# v3-half.net
KiCad netlist of a schematic drawn in EAGLE
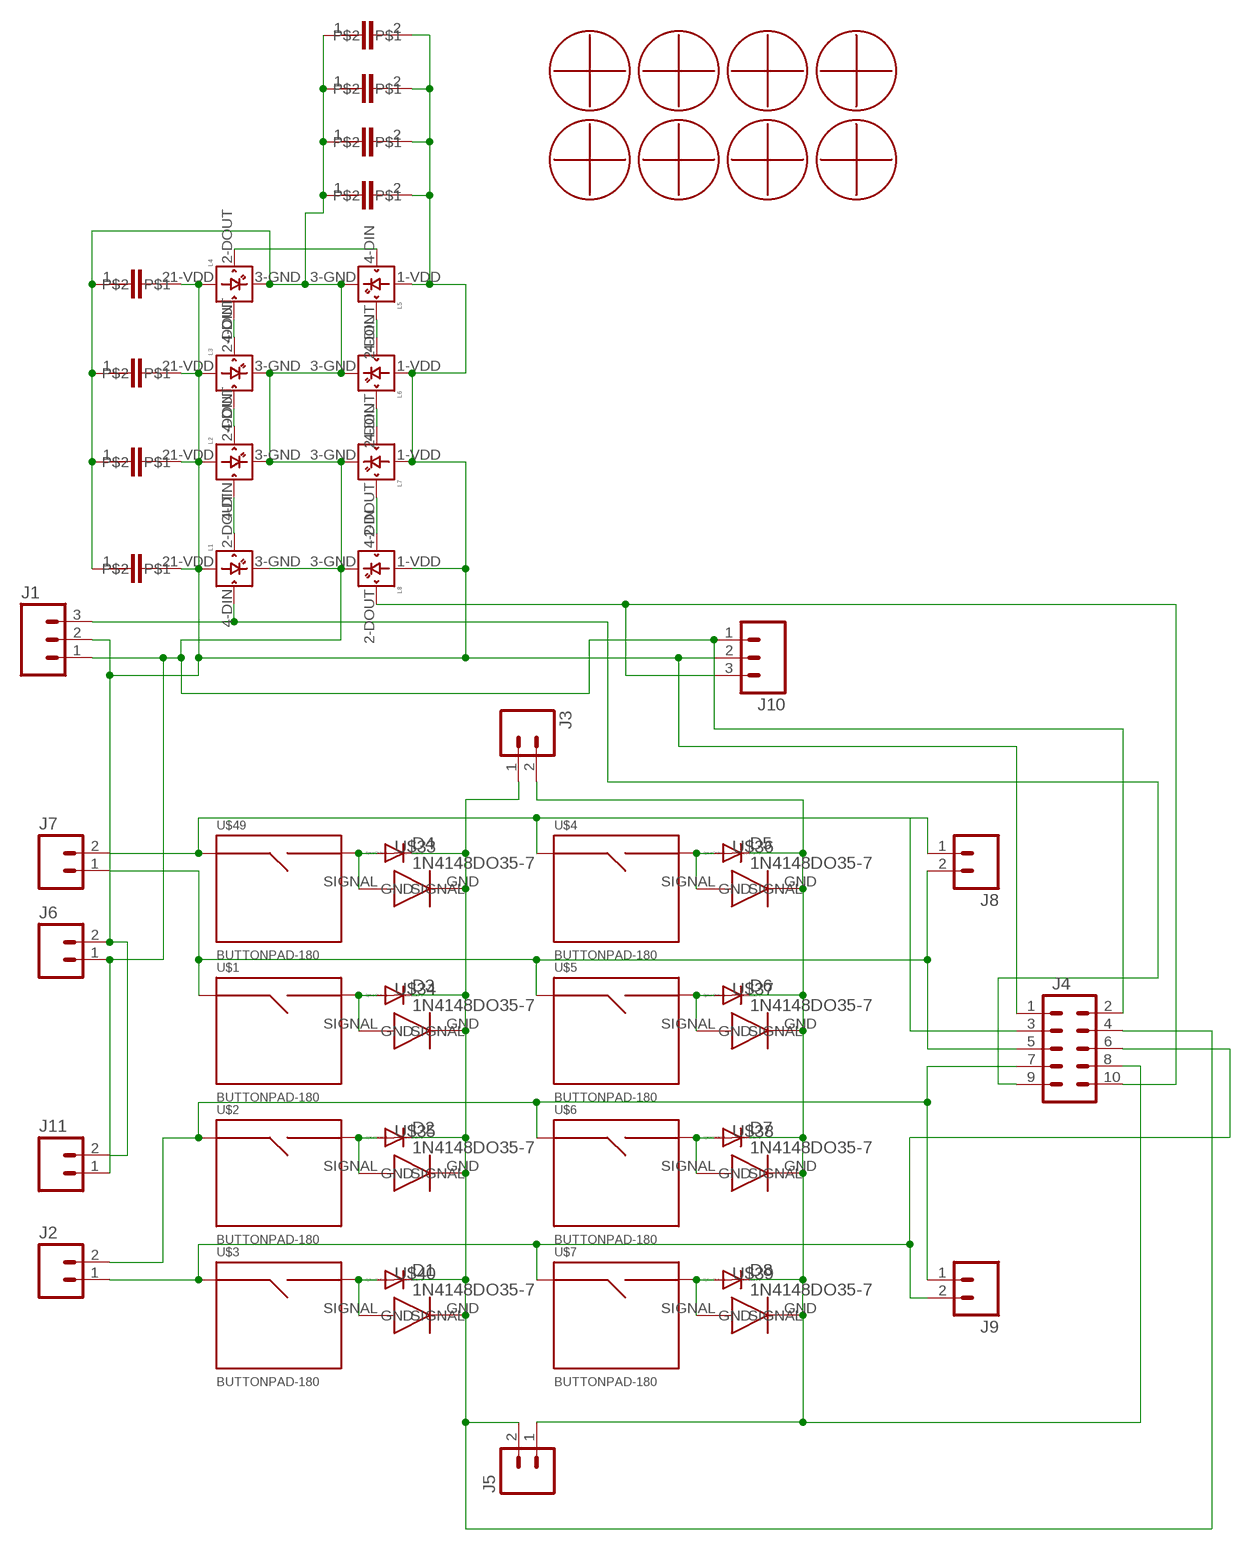
[diagram p0: schematic, sheet 1]

(export (version "E")
  (design (tool "Eeschema 10.0.6"))
  (components
    (comp (ref "D1")
      (value "1N4148DO35-7")
      (footprint "eagle-import:DO35-7")
      (libsource (lib "eagle-import") (part "1N4148DO35-7"))
    )
    (comp (ref "D2")
      (value "1N4148DO35-7")
      (footprint "eagle-import:DO35-7")
      (libsource (lib "eagle-import") (part "1N4148DO35-7"))
    )
    (comp (ref "D3")
      (value "1N4148DO35-7")
      (footprint "eagle-import:DO35-7")
      (libsource (lib "eagle-import") (part "1N4148DO35-7"))
    )
    (comp (ref "D4")
      (value "1N4148DO35-7")
      (footprint "eagle-import:DO35-7")
      (libsource (lib "eagle-import") (part "1N4148DO35-7"))
    )
    (comp (ref "D5")
      (value "1N4148DO35-7")
      (footprint "eagle-import:DO35-7")
      (libsource (lib "eagle-import") (part "1N4148DO35-7"))
    )
    (comp (ref "D6")
      (value "1N4148DO35-7")
      (footprint "eagle-import:DO35-7")
      (libsource (lib "eagle-import") (part "1N4148DO35-7"))
    )
    (comp (ref "D7")
      (value "1N4148DO35-7")
      (footprint "eagle-import:DO35-7")
      (libsource (lib "eagle-import") (part "1N4148DO35-7"))
    )
    (comp (ref "D8")
      (value "1N4148DO35-7")
      (footprint "eagle-import:DO35-7")
      (libsource (lib "eagle-import") (part "1N4148DO35-7"))
    )
    (comp (ref "J1")
      (value "M031X03_NO_SILK")
      (footprint "eagle-import:1X03_NO_SILK")
      (libsource (lib "eagle-import") (part "M031X03_NO_SILK"))
    )
    (comp (ref "J2")
      (value "M021X02_NO_SILK")
      (footprint "eagle-import:1X02_NO_SILK")
      (libsource (lib "eagle-import") (part "M021X02_NO_SILK"))
    )
    (comp (ref "J3")
      (value "M021X02_NO_SILK")
      (footprint "eagle-import:1X02_NO_SILK")
      (libsource (lib "eagle-import") (part "M021X02_NO_SILK"))
    )
    (comp (ref "J4")
      (value "M05X2NO_SILK")
      (footprint "eagle-import:2X5_NOSILK")
      (libsource (lib "eagle-import") (part "M05X2NO_SILK"))
    )
    (comp (ref "J5")
      (value "M021X02_NO_SILK")
      (footprint "eagle-import:1X02_NO_SILK")
      (libsource (lib "eagle-import") (part "M021X02_NO_SILK"))
    )
    (comp (ref "J6")
      (value "M021X02_NO_SILK")
      (footprint "eagle-import:1X02_NO_SILK")
      (libsource (lib "eagle-import") (part "M021X02_NO_SILK"))
    )
    (comp (ref "J7")
      (value "M021X02_NO_SILK")
      (footprint "eagle-import:1X02_NO_SILK")
      (libsource (lib "eagle-import") (part "M021X02_NO_SILK"))
    )
    (comp (ref "J8")
      (value "M021X02_NO_SILK")
      (footprint "eagle-import:1X02_NO_SILK")
      (libsource (lib "eagle-import") (part "M021X02_NO_SILK"))
    )
    (comp (ref "J9")
      (value "M021X02_NO_SILK")
      (footprint "eagle-import:1X02_NO_SILK")
      (libsource (lib "eagle-import") (part "M021X02_NO_SILK"))
    )
    (comp (ref "J10")
      (value "M031X03_NO_SILK")
      (footprint "eagle-import:1X03_NO_SILK")
      (libsource (lib "eagle-import") (part "M031X03_NO_SILK"))
    )
    (comp (ref "J11")
      (value "M021X02_NO_SILK")
      (footprint "eagle-import:1X02_NO_SILK")
      (libsource (lib "eagle-import") (part "M021X02_NO_SILK"))
    )
    (comp (ref "L1")
      (value "WS2812B")
      (footprint "eagle-import:WS2812B")
      (libsource (lib "eagle-import") (part "WS2812B"))
    )
    (comp (ref "L2")
      (value "WS2812B")
      (footprint "eagle-import:WS2812B")
      (libsource (lib "eagle-import") (part "WS2812B"))
    )
    (comp (ref "L3")
      (value "WS2812B")
      (footprint "eagle-import:WS2812B")
      (libsource (lib "eagle-import") (part "WS2812B"))
    )
    (comp (ref "L4")
      (value "WS2812B")
      (footprint "eagle-import:WS2812B")
      (libsource (lib "eagle-import") (part "WS2812B"))
    )
    (comp (ref "L5")
      (value "WS2812B")
      (footprint "eagle-import:WS2812B")
      (libsource (lib "eagle-import") (part "WS2812B"))
    )
    (comp (ref "L6")
      (value "WS2812B")
      (footprint "eagle-import:WS2812B")
      (libsource (lib "eagle-import") (part "WS2812B"))
    )
    (comp (ref "L7")
      (value "WS2812B")
      (footprint "eagle-import:WS2812B")
      (libsource (lib "eagle-import") (part "WS2812B"))
    )
    (comp (ref "L8")
      (value "WS2812B")
      (footprint "eagle-import:WS2812B")
      (libsource (lib "eagle-import") (part "WS2812B"))
    )
    (comp (ref "U$1")
      (value "BUTTONPAD-180")
      (footprint "eagle-import:BUTTONPAD-180")
      (libsource (lib "eagle-import") (part "BUTTONPAD-180"))
    )
    (comp (ref "U$2")
      (value "BUTTONPAD-180")
      (footprint "eagle-import:BUTTONPAD-180")
      (libsource (lib "eagle-import") (part "BUTTONPAD-180"))
    )
    (comp (ref "U$3")
      (value "BUTTONPAD-180")
      (footprint "eagle-import:BUTTONPAD-180")
      (libsource (lib "eagle-import") (part "BUTTONPAD-180"))
    )
    (comp (ref "U$4")
      (value "BUTTONPAD-180")
      (footprint "eagle-import:BUTTONPAD-180")
      (libsource (lib "eagle-import") (part "BUTTONPAD-180"))
    )
    (comp (ref "U$5")
      (value "BUTTONPAD-180")
      (footprint "eagle-import:BUTTONPAD-180")
      (libsource (lib "eagle-import") (part "BUTTONPAD-180"))
    )
    (comp (ref "U$6")
      (value "BUTTONPAD-180")
      (footprint "eagle-import:BUTTONPAD-180")
      (libsource (lib "eagle-import") (part "BUTTONPAD-180"))
    )
    (comp (ref "U$7")
      (value "BUTTONPAD-180")
      (footprint "eagle-import:BUTTONPAD-180")
      (libsource (lib "eagle-import") (part "BUTTONPAD-180"))
    )
    (comp (ref "U$8")
      (value "M25MOUNT")
      (footprint "eagle-import:M25MOUNT")
      (libsource (lib "eagle-import") (part "M25MOUNT"))
    )
    (comp (ref "U$9")
      (value "M25MOUNT")
      (footprint "eagle-import:M25MOUNT")
      (libsource (lib "eagle-import") (part "M25MOUNT"))
    )
    (comp (ref "U$10")
      (value "M25MOUNT")
      (footprint "eagle-import:M25MOUNT")
      (libsource (lib "eagle-import") (part "M25MOUNT"))
    )
    (comp (ref "U$11")
      (value "M25MOUNT")
      (footprint "eagle-import:M25MOUNT")
      (libsource (lib "eagle-import") (part "M25MOUNT"))
    )
    (comp (ref "U$12")
      (value "M25MOUNT")
      (footprint "eagle-import:M25MOUNT")
      (libsource (lib "eagle-import") (part "M25MOUNT"))
    )
    (comp (ref "U$13")
      (value "M25MOUNT")
      (footprint "eagle-import:M25MOUNT")
      (libsource (lib "eagle-import") (part "M25MOUNT"))
    )
    (comp (ref "U$14")
      (value "M25MOUNT")
      (footprint "eagle-import:M25MOUNT")
      (libsource (lib "eagle-import") (part "M25MOUNT"))
    )
    (comp (ref "U$15")
      (value "M25MOUNT")
      (footprint "eagle-import:M25MOUNT")
      (libsource (lib "eagle-import") (part "M25MOUNT"))
    )
    (comp (ref "U$17")
      (value "0805CAP")
      (footprint "eagle-import:0805")
      (libsource (lib "eagle-import") (part "0805CAP"))
    )
    (comp (ref "U$18")
      (value "0805CAP")
      (footprint "eagle-import:0805")
      (libsource (lib "eagle-import") (part "0805CAP"))
    )
    (comp (ref "U$19")
      (value "0805CAP")
      (footprint "eagle-import:0805")
      (libsource (lib "eagle-import") (part "0805CAP"))
    )
    (comp (ref "U$20")
      (value "0805CAP")
      (footprint "eagle-import:0805")
      (libsource (lib "eagle-import") (part "0805CAP"))
    )
    (comp (ref "U$25")
      (value "0805CAP")
      (footprint "eagle-import:0805")
      (libsource (lib "eagle-import") (part "0805CAP"))
    )
    (comp (ref "U$26")
      (value "0805CAP")
      (footprint "eagle-import:0805")
      (libsource (lib "eagle-import") (part "0805CAP"))
    )
    (comp (ref "U$27")
      (value "0805CAP")
      (footprint "eagle-import:0805")
      (libsource (lib "eagle-import") (part "0805CAP"))
    )
    (comp (ref "U$28")
      (value "0805CAP")
      (footprint "eagle-import:0805")
      (libsource (lib "eagle-import") (part "0805CAP"))
    )
    (comp (ref "U$33")
      (value "4148DIODE")
      (footprint "eagle-import:SOD-323")
      (libsource (lib "eagle-import") (part "4148DIODE"))
    )
    (comp (ref "U$34")
      (value "4148DIODE")
      (footprint "eagle-import:SOD-323")
      (libsource (lib "eagle-import") (part "4148DIODE"))
    )
    (comp (ref "U$35")
      (value "4148DIODE")
      (footprint "eagle-import:SOD-323")
      (libsource (lib "eagle-import") (part "4148DIODE"))
    )
    (comp (ref "U$36")
      (value "4148DIODE")
      (footprint "eagle-import:SOD-323")
      (libsource (lib "eagle-import") (part "4148DIODE"))
    )
    (comp (ref "U$37")
      (value "4148DIODE")
      (footprint "eagle-import:SOD-323")
      (libsource (lib "eagle-import") (part "4148DIODE"))
    )
    (comp (ref "U$38")
      (value "4148DIODE")
      (footprint "eagle-import:SOD-323")
      (libsource (lib "eagle-import") (part "4148DIODE"))
    )
    (comp (ref "U$39")
      (value "4148DIODE")
      (footprint "eagle-import:SOD-323")
      (libsource (lib "eagle-import") (part "4148DIODE"))
    )
    (comp (ref "U$40")
      (value "4148DIODE")
      (footprint "eagle-import:SOD-323")
      (libsource (lib "eagle-import") (part "4148DIODE"))
    )
    (comp (ref "U$49")
      (value "BUTTONPAD-180")
      (footprint "eagle-import:BUTTONPAD-180")
      (libsource (lib "eagle-import") (part "BUTTONPAD-180"))
    )
  )
  (nets
    (net (code "1") (name "Net-(D1-PadC)") (class "Default")
      (node (ref "D1") (pin "C") (pinfunction "C_C") (pintype "passive"))
      (node (ref "D2") (pin "C") (pinfunction "C_C") (pintype "passive"))
      (node (ref "D3") (pin "C") (pinfunction "C_C") (pintype "passive"))
      (node (ref "D4") (pin "C") (pinfunction "C_C") (pintype "passive"))
      (node (ref "J3") (pin "1") (pinfunction "1_1") (pintype "passive"))
      (node (ref "J4") (pin "4") (pinfunction "4_4") (pintype "passive"))
      (node (ref "J5") (pin "2") (pinfunction "2_2") (pintype "passive"))
      (node (ref "U$33") (pin "GND") (pinfunction "GND_GND") (pintype "bidirectional"))
      (node (ref "U$34") (pin "GND") (pinfunction "GND_GND") (pintype "bidirectional"))
      (node (ref "U$35") (pin "GND") (pinfunction "GND_GND") (pintype "bidirectional"))
      (node (ref "U$40") (pin "GND") (pinfunction "GND_GND") (pintype "bidirectional"))
    )
    (net (code "2") (name "Net-(D5-PadC)") (class "Default")
      (node (ref "D5") (pin "C") (pinfunction "C_C") (pintype "passive"))
      (node (ref "D6") (pin "C") (pinfunction "C_C") (pintype "passive"))
      (node (ref "D7") (pin "C") (pinfunction "C_C") (pintype "passive"))
      (node (ref "D8") (pin "C") (pinfunction "C_C") (pintype "passive"))
      (node (ref "J3") (pin "2") (pinfunction "2_2") (pintype "passive"))
      (node (ref "J4") (pin "8") (pinfunction "8_8") (pintype "passive"))
      (node (ref "J5") (pin "1") (pinfunction "1_1") (pintype "passive"))
      (node (ref "U$36") (pin "GND") (pinfunction "GND_GND") (pintype "bidirectional"))
      (node (ref "U$37") (pin "GND") (pinfunction "GND_GND") (pintype "bidirectional"))
      (node (ref "U$38") (pin "GND") (pinfunction "GND_GND") (pintype "bidirectional"))
      (node (ref "U$39") (pin "GND") (pinfunction "GND_GND") (pintype "bidirectional"))
    )
    (net (code "3") (name "Net-(L1-DIN)") (class "Default")
      (node (ref "J1") (pin "3") (pinfunction "3_3") (pintype "passive"))
      (node (ref "J4") (pin "9") (pinfunction "9_9") (pintype "passive"))
      (node (ref "L1") (pin "4-DIN") (pinfunction "DIN_4-DIN") (pintype "input"))
    )
    (net (code "4") (name "Net-(L1-DOUT)") (class "Default")
      (node (ref "L1") (pin "2-DOUT") (pinfunction "DOUT_2-DOUT") (pintype "output"))
      (node (ref "L2") (pin "4-DIN") (pinfunction "DIN_4-DIN") (pintype "input"))
    )
    (net (code "5") (name "Net-(L1-GND)") (class "Default")
      (node (ref "J1") (pin "1") (pinfunction "1_1") (pintype "passive"))
      (node (ref "J10") (pin "1") (pinfunction "1_1") (pintype "passive"))
      (node (ref "J11") (pin "1") (pinfunction "1_1") (pintype "passive"))
      (node (ref "J4") (pin "2") (pinfunction "2_2") (pintype "passive"))
      (node (ref "J6") (pin "1") (pinfunction "1_1") (pintype "passive"))
      (node (ref "L1") (pin "3-GND") (pinfunction "GND_3-GND") (pintype "bidirectional"))
      (node (ref "L2") (pin "3-GND") (pinfunction "GND_3-GND") (pintype "bidirectional"))
      (node (ref "L3") (pin "3-GND") (pinfunction "GND_3-GND") (pintype "bidirectional"))
      (node (ref "L4") (pin "3-GND") (pinfunction "GND_3-GND") (pintype "bidirectional"))
      (node (ref "L5") (pin "3-GND") (pinfunction "GND_3-GND") (pintype "bidirectional"))
      (node (ref "L6") (pin "3-GND") (pinfunction "GND_3-GND") (pintype "bidirectional"))
      (node (ref "L7") (pin "3-GND") (pinfunction "GND_3-GND") (pintype "bidirectional"))
      (node (ref "L8") (pin "3-GND") (pinfunction "GND_3-GND") (pintype "bidirectional"))
      (node (ref "U$17") (pin "1") (pinfunction "P$1_1") (pintype "bidirectional"))
      (node (ref "U$18") (pin "1") (pinfunction "P$1_1") (pintype "bidirectional"))
      (node (ref "U$19") (pin "1") (pinfunction "P$1_1") (pintype "bidirectional"))
      (node (ref "U$20") (pin "1") (pinfunction "P$1_1") (pintype "bidirectional"))
      (node (ref "U$25") (pin "1") (pinfunction "P$1_1") (pintype "bidirectional"))
      (node (ref "U$26") (pin "1") (pinfunction "P$1_1") (pintype "bidirectional"))
      (node (ref "U$27") (pin "1") (pinfunction "P$1_1") (pintype "bidirectional"))
      (node (ref "U$28") (pin "1") (pinfunction "P$1_1") (pintype "bidirectional"))
    )
    (net (code "6") (name "Net-(L1-VDD)") (class "Default")
      (node (ref "J1") (pin "2") (pinfunction "2_2") (pintype "passive"))
      (node (ref "J10") (pin "2") (pinfunction "2_2") (pintype "passive"))
      (node (ref "J11") (pin "2") (pinfunction "2_2") (pintype "passive"))
      (node (ref "J4") (pin "1") (pinfunction "1_1") (pintype "passive"))
      (node (ref "J6") (pin "2") (pinfunction "2_2") (pintype "passive"))
      (node (ref "L1") (pin "1-VDD") (pinfunction "VDD_1-VDD") (pintype "bidirectional"))
      (node (ref "L2") (pin "1-VDD") (pinfunction "VDD_1-VDD") (pintype "bidirectional"))
      (node (ref "L3") (pin "1-VDD") (pinfunction "VDD_1-VDD") (pintype "bidirectional"))
      (node (ref "L4") (pin "1-VDD") (pinfunction "VDD_1-VDD") (pintype "bidirectional"))
      (node (ref "L5") (pin "1-VDD") (pinfunction "VDD_1-VDD") (pintype "bidirectional"))
      (node (ref "L6") (pin "1-VDD") (pinfunction "VDD_1-VDD") (pintype "bidirectional"))
      (node (ref "L7") (pin "1-VDD") (pinfunction "VDD_1-VDD") (pintype "bidirectional"))
      (node (ref "L8") (pin "1-VDD") (pinfunction "VDD_1-VDD") (pintype "bidirectional"))
      (node (ref "U$17") (pin "2") (pinfunction "P$2_2") (pintype "bidirectional"))
      (node (ref "U$18") (pin "2") (pinfunction "P$2_2") (pintype "bidirectional"))
      (node (ref "U$19") (pin "2") (pinfunction "P$2_2") (pintype "bidirectional"))
      (node (ref "U$20") (pin "2") (pinfunction "P$2_2") (pintype "bidirectional"))
      (node (ref "U$25") (pin "2") (pinfunction "P$2_2") (pintype "bidirectional"))
      (node (ref "U$26") (pin "2") (pinfunction "P$2_2") (pintype "bidirectional"))
      (node (ref "U$27") (pin "2") (pinfunction "P$2_2") (pintype "bidirectional"))
      (node (ref "U$28") (pin "2") (pinfunction "P$2_2") (pintype "bidirectional"))
    )
    (net (code "7") (name "Net-(L2-DOUT)") (class "Default")
      (node (ref "L2") (pin "2-DOUT") (pinfunction "DOUT_2-DOUT") (pintype "output"))
      (node (ref "L3") (pin "4-DIN") (pinfunction "DIN_4-DIN") (pintype "input"))
    )
    (net (code "8") (name "Net-(L3-DOUT)") (class "Default")
      (node (ref "L3") (pin "2-DOUT") (pinfunction "DOUT_2-DOUT") (pintype "output"))
      (node (ref "L4") (pin "4-DIN") (pinfunction "DIN_4-DIN") (pintype "input"))
    )
    (net (code "9") (name "Net-(L4-DOUT)") (class "Default")
      (node (ref "L4") (pin "2-DOUT") (pinfunction "DOUT_2-DOUT") (pintype "output"))
      (node (ref "L5") (pin "4-DIN") (pinfunction "DIN_4-DIN") (pintype "input"))
    )
    (net (code "10") (name "Net-(L5-DOUT)") (class "Default")
      (node (ref "L5") (pin "2-DOUT") (pinfunction "DOUT_2-DOUT") (pintype "output"))
      (node (ref "L6") (pin "4-DIN") (pinfunction "DIN_4-DIN") (pintype "input"))
    )
    (net (code "11") (name "Net-(L6-DOUT)") (class "Default")
      (node (ref "L6") (pin "2-DOUT") (pinfunction "DOUT_2-DOUT") (pintype "output"))
      (node (ref "L7") (pin "4-DIN") (pinfunction "DIN_4-DIN") (pintype "input"))
    )
    (net (code "12") (name "Net-(L7-DOUT)") (class "Default")
      (node (ref "L7") (pin "2-DOUT") (pinfunction "DOUT_2-DOUT") (pintype "output"))
      (node (ref "L8") (pin "4-DIN") (pinfunction "DIN_4-DIN") (pintype "input"))
    )
    (net (code "13") (name "Net-(L8-DOUT)") (class "Default")
      (node (ref "J10") (pin "3") (pinfunction "3_3") (pintype "passive"))
      (node (ref "J4") (pin "10") (pinfunction "10_10") (pintype "passive"))
      (node (ref "L8") (pin "2-DOUT") (pinfunction "DOUT_2-DOUT") (pintype "output"))
    )
    (net (code "14") (name "Net-(U$1-SIG1)") (class "Default")
      (node (ref "J4") (pin "5") (pinfunction "5_5") (pintype "passive"))
      (node (ref "J7") (pin "1") (pinfunction "1_1") (pintype "passive"))
      (node (ref "J8") (pin "2") (pinfunction "2_2") (pintype "passive"))
      (node (ref "U$1") (pin "P$1") (pinfunction "SIG1_P$1") (pintype "bidirectional"))
      (node (ref "U$5") (pin "P$1") (pinfunction "SIG1_P$1") (pintype "bidirectional"))
    )
    (net (code "15") (name "Net-(U$1-SIG2)") (class "Default")
      (node (ref "D3") (pin "A") (pinfunction "A_A") (pintype "passive"))
      (node (ref "U$1") (pin "P$2") (pinfunction "SIG2_P$2") (pintype "bidirectional"))
      (node (ref "U$34") (pin "SIGNAL") (pinfunction "SIGNAL_SIGNAL") (pintype "bidirectional"))
    )
    (net (code "16") (name "Net-(U$2-SIG1)") (class "Default")
      (node (ref "J2") (pin "2") (pinfunction "2_2") (pintype "passive"))
      (node (ref "J4") (pin "7") (pinfunction "7_7") (pintype "passive"))
      (node (ref "J9") (pin "1") (pinfunction "1_1") (pintype "passive"))
      (node (ref "U$2") (pin "P$1") (pinfunction "SIG1_P$1") (pintype "bidirectional"))
      (node (ref "U$6") (pin "P$1") (pinfunction "SIG1_P$1") (pintype "bidirectional"))
    )
    (net (code "17") (name "Net-(U$2-SIG2)") (class "Default")
      (node (ref "D2") (pin "A") (pinfunction "A_A") (pintype "passive"))
      (node (ref "U$2") (pin "P$2") (pinfunction "SIG2_P$2") (pintype "bidirectional"))
      (node (ref "U$35") (pin "SIGNAL") (pinfunction "SIGNAL_SIGNAL") (pintype "bidirectional"))
    )
    (net (code "18") (name "Net-(U$3-SIG1)") (class "Default")
      (node (ref "J2") (pin "1") (pinfunction "1_1") (pintype "passive"))
      (node (ref "J4") (pin "6") (pinfunction "6_6") (pintype "passive"))
      (node (ref "J9") (pin "2") (pinfunction "2_2") (pintype "passive"))
      (node (ref "U$3") (pin "P$1") (pinfunction "SIG1_P$1") (pintype "bidirectional"))
      (node (ref "U$7") (pin "P$1") (pinfunction "SIG1_P$1") (pintype "bidirectional"))
    )
    (net (code "19") (name "Net-(U$3-SIG2)") (class "Default")
      (node (ref "D1") (pin "A") (pinfunction "A_A") (pintype "passive"))
      (node (ref "U$3") (pin "P$2") (pinfunction "SIG2_P$2") (pintype "bidirectional"))
      (node (ref "U$40") (pin "SIGNAL") (pinfunction "SIGNAL_SIGNAL") (pintype "bidirectional"))
    )
    (net (code "20") (name "Net-(U$4-SIG1)") (class "Default")
      (node (ref "J4") (pin "3") (pinfunction "3_3") (pintype "passive"))
      (node (ref "J7") (pin "2") (pinfunction "2_2") (pintype "passive"))
      (node (ref "J8") (pin "1") (pinfunction "1_1") (pintype "passive"))
      (node (ref "U$4") (pin "P$1") (pinfunction "SIG1_P$1") (pintype "bidirectional"))
      (node (ref "U$49") (pin "P$1") (pinfunction "SIG1_P$1") (pintype "bidirectional"))
    )
    (net (code "21") (name "Net-(U$4-SIG2)") (class "Default")
      (node (ref "D5") (pin "A") (pinfunction "A_A") (pintype "passive"))
      (node (ref "U$36") (pin "SIGNAL") (pinfunction "SIGNAL_SIGNAL") (pintype "bidirectional"))
      (node (ref "U$4") (pin "P$2") (pinfunction "SIG2_P$2") (pintype "bidirectional"))
    )
    (net (code "22") (name "Net-(U$5-SIG2)") (class "Default")
      (node (ref "D6") (pin "A") (pinfunction "A_A") (pintype "passive"))
      (node (ref "U$37") (pin "SIGNAL") (pinfunction "SIGNAL_SIGNAL") (pintype "bidirectional"))
      (node (ref "U$5") (pin "P$2") (pinfunction "SIG2_P$2") (pintype "bidirectional"))
    )
    (net (code "23") (name "Net-(U$6-SIG2)") (class "Default")
      (node (ref "D7") (pin "A") (pinfunction "A_A") (pintype "passive"))
      (node (ref "U$38") (pin "SIGNAL") (pinfunction "SIGNAL_SIGNAL") (pintype "bidirectional"))
      (node (ref "U$6") (pin "P$2") (pinfunction "SIG2_P$2") (pintype "bidirectional"))
    )
    (net (code "24") (name "Net-(U$7-SIG2)") (class "Default")
      (node (ref "D8") (pin "A") (pinfunction "A_A") (pintype "passive"))
      (node (ref "U$39") (pin "SIGNAL") (pinfunction "SIGNAL_SIGNAL") (pintype "bidirectional"))
      (node (ref "U$7") (pin "P$2") (pinfunction "SIG2_P$2") (pintype "bidirectional"))
    )
    (net (code "25") (name "Net-(U$49-SIG2)") (class "Default")
      (node (ref "D4") (pin "A") (pinfunction "A_A") (pintype "passive"))
      (node (ref "U$33") (pin "SIGNAL") (pinfunction "SIGNAL_SIGNAL") (pintype "bidirectional"))
      (node (ref "U$49") (pin "P$2") (pinfunction "SIG2_P$2") (pintype "bidirectional"))
    )
  )
)
